# 9DOF-Razor-v23.net
KiCad netlist of a schematic drawn in EAGLE
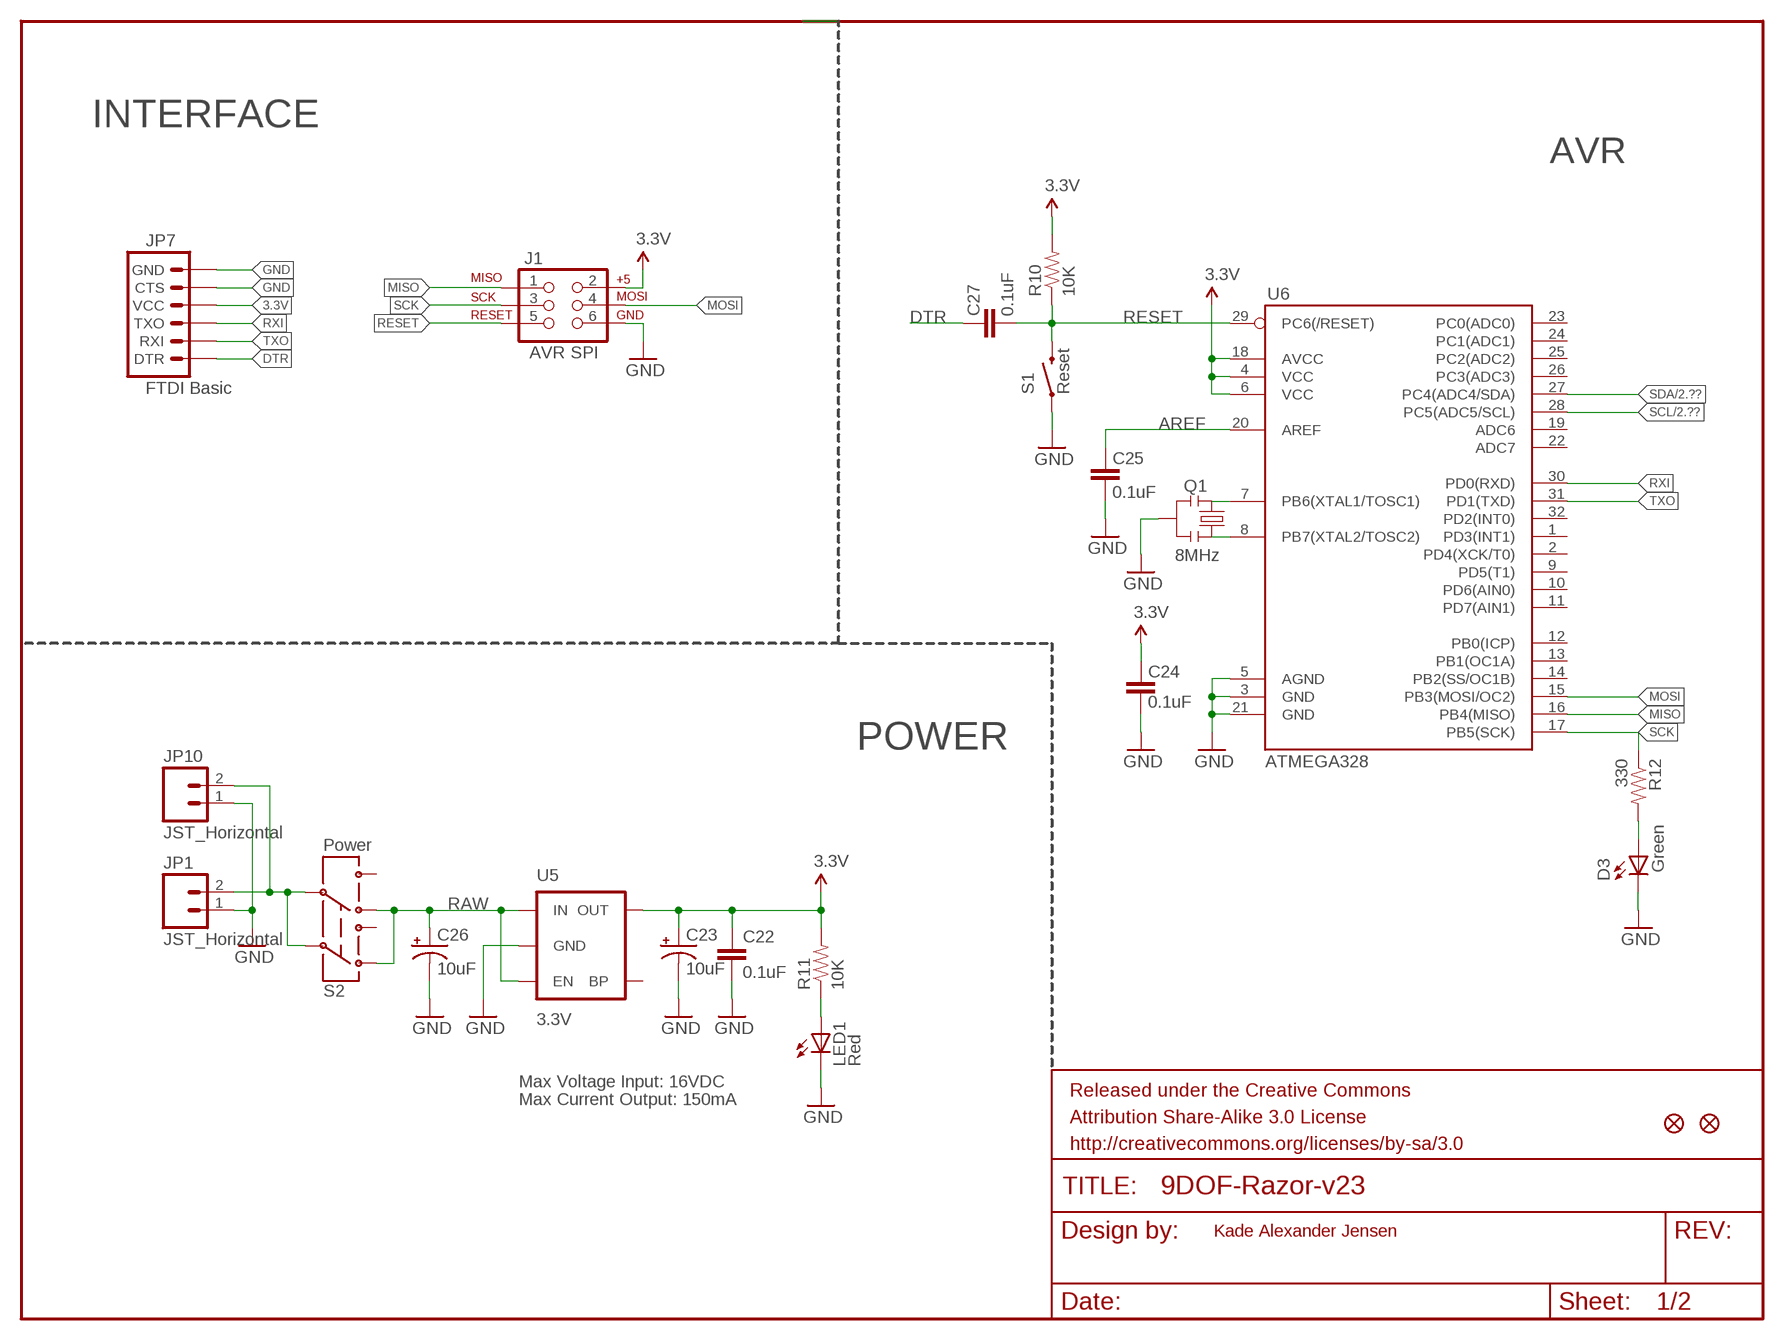
[diagram p0: schematic, sheet 1]
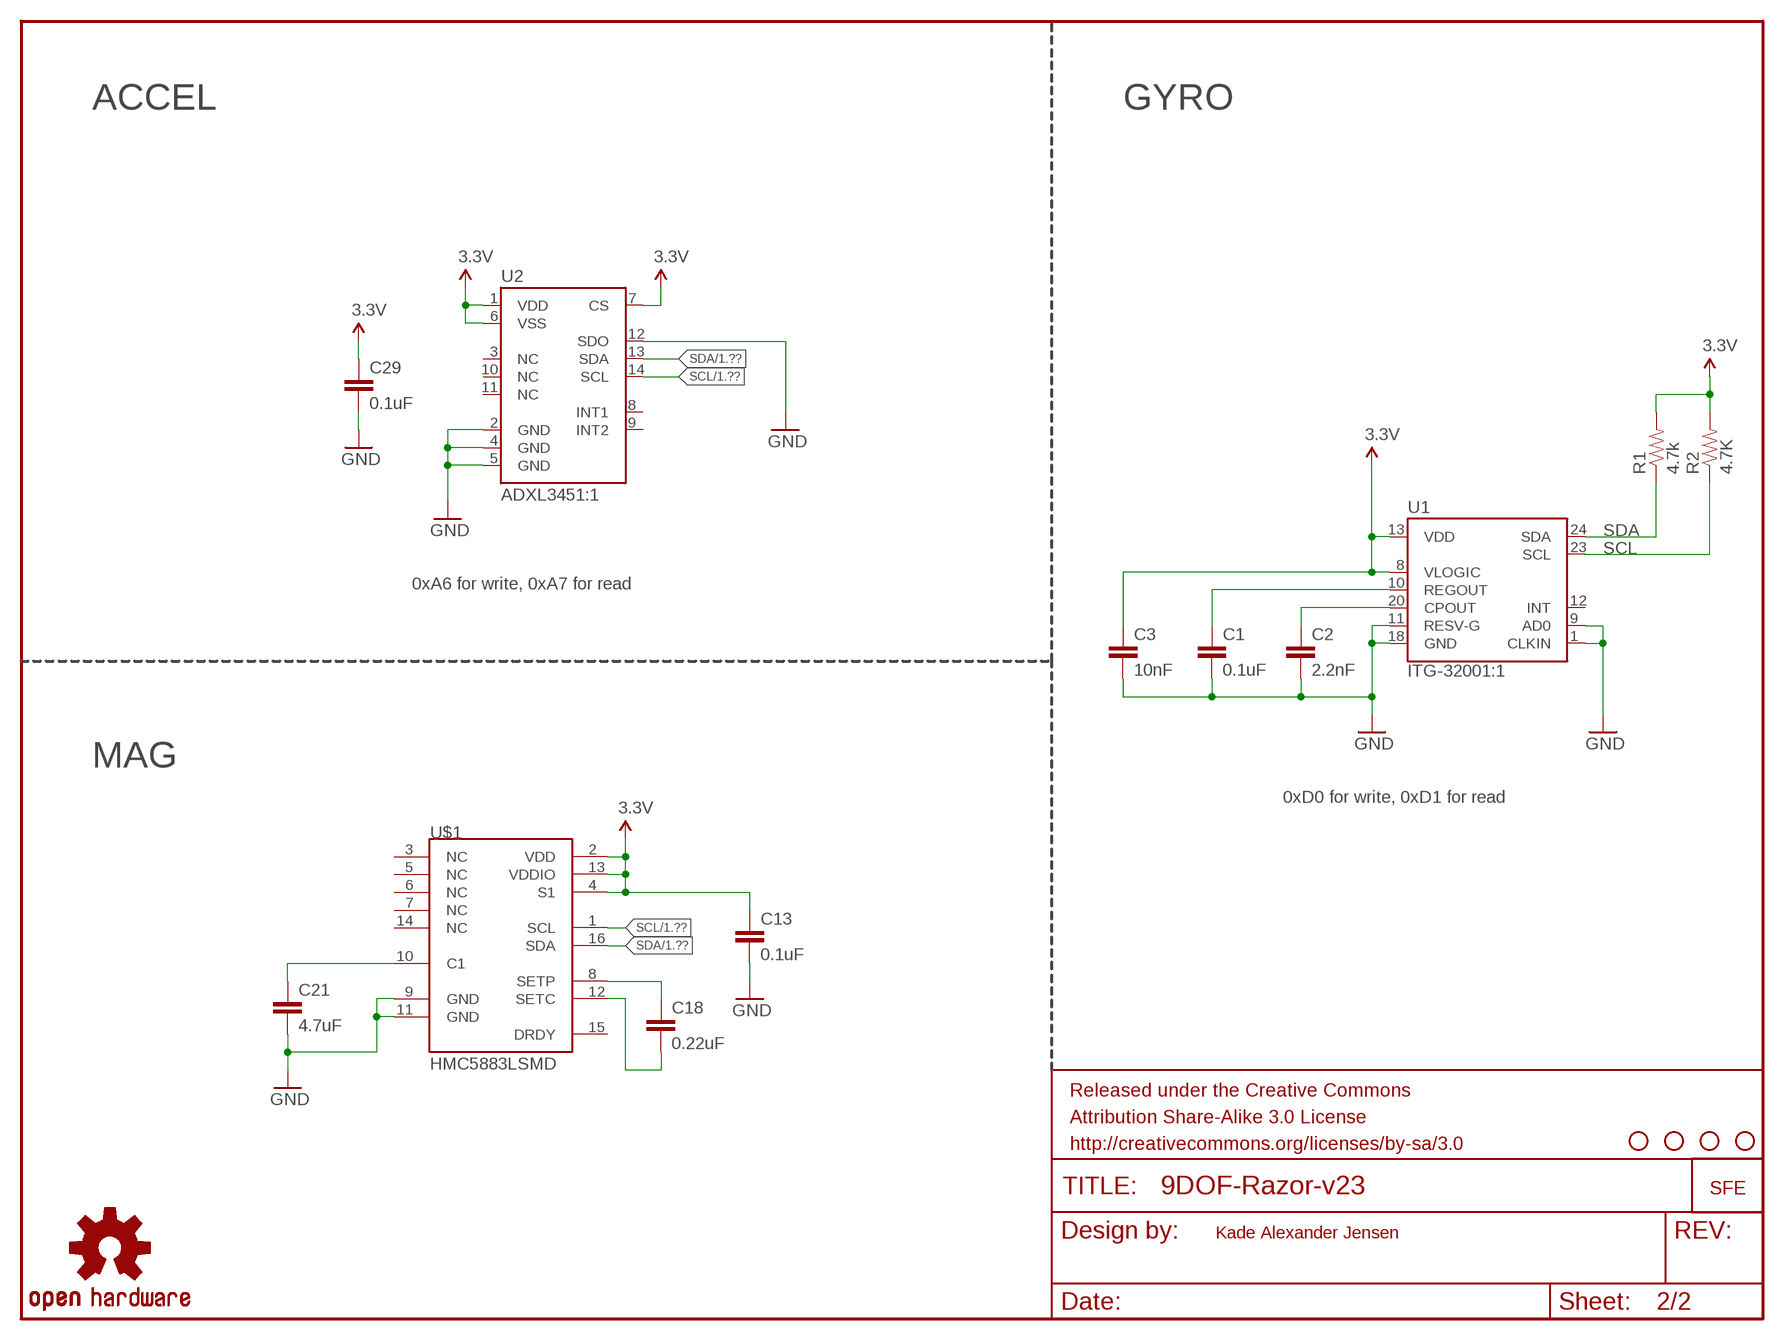
[diagram p1: schematic, sheet 2]

(export (version "E")
  (design (tool "Eeschema 10.0.6"))
  (components
    (comp (ref "C22")
      (value "0.1uF")
      (footprint "eagle-import:0603-CAP")
      (libsource (lib "eagle-import") (part "CAP0603-CAP"))
    )
    (comp (ref "C23")
      (value "10uF")
      (footprint "eagle-import:EIA3216")
      (libsource (lib "eagle-import") (part "CAP_POL1206"))
    )
    (comp (ref "C24")
      (value "0.1uF")
      (footprint "eagle-import:0603-CAP")
      (libsource (lib "eagle-import") (part "CAP0603-CAP"))
    )
    (comp (ref "C25")
      (value "0.1uF")
      (footprint "eagle-import:0603-CAP")
      (libsource (lib "eagle-import") (part "CAP0603-CAP"))
    )
    (comp (ref "C26")
      (value "10uF")
      (footprint "eagle-import:EIA3216")
      (libsource (lib "eagle-import") (part "CAP_POL1206"))
    )
    (comp (ref "C27")
      (value "0.1uF")
      (footprint "eagle-import:0603-CAP")
      (libsource (lib "eagle-import") (part "CAP0603-CAP"))
    )
    (comp (ref "D3")
      (value "Green")
      (footprint "eagle-import:LED-0603")
      (libsource (lib "eagle-import") (part "LED0603"))
    )
    (comp (ref "J1")
      (value "AVR_SPI_PRG_6PTH")
      (footprint "eagle-import:2X3")
      (libsource (lib "eagle-import") (part "AVR_SPI_PRG_6PTH"))
    )
    (comp (ref "JP1")
      (value "JST_Horizontal")
      (footprint "eagle-import:JST-2-SMD")
      (libsource (lib "eagle-import") (part "M02-JST-2MM-SMT"))
    )
    (comp (ref "JP7")
      (value "FTDI Basic")
      (footprint "eagle-import:1X06")
      (libsource (lib "eagle-import") (part "ARDUINO_SERIAL_PROGRAMPTH"))
    )
    (comp (ref "JP10")
      (value "JST_Horizontal")
      (footprint "eagle-import:1X02")
      (libsource (lib "eagle-import") (part "M02PTH"))
    )
    (comp (ref "JP11")
      (value "FIDUCIAL1X2.5")
      (footprint "eagle-import:FIDUCIAL-1X2.5")
      (libsource (lib "eagle-import") (part "FIDUCIAL1X2.5"))
    )
    (comp (ref "JP12")
      (value "FIDUCIAL1X2.5")
      (footprint "eagle-import:FIDUCIAL-1X2.5")
      (libsource (lib "eagle-import") (part "FIDUCIAL1X2.5"))
    )
    (comp (ref "LED1")
      (value "Red")
      (footprint "eagle-import:LED-0603")
      (libsource (lib "eagle-import") (part "LED0603"))
    )
    (comp (ref "Q1")
      (value "8MHz")
      (footprint "eagle-import:RESONATOR-SMD")
      (libsource (lib "eagle-import") (part "RESONATORSMD"))
    )
    (comp (ref "R10")
      (value "10K")
      (footprint "eagle-import:0603-RES")
      (libsource (lib "eagle-import") (part "RESISTOR0603-RES"))
    )
    (comp (ref "R11")
      (value "10K")
      (footprint "eagle-import:0603-RES")
      (libsource (lib "eagle-import") (part "RESISTOR0603-RES"))
    )
    (comp (ref "R12")
      (value "330")
      (footprint "eagle-import:0603-RES")
      (libsource (lib "eagle-import") (part "RESISTOR0603-RES"))
    )
    (comp (ref "S1")
      (value "Reset")
      (footprint "eagle-import:TACTILE_SWITCH_SMD")
      (libsource (lib "eagle-import") (part "SWITCH-MOMENTARY-2SMD"))
    )
    (comp (ref "S2")
      (value "Power")
      (footprint "eagle-import:AYZ0202")
      (libsource (lib "eagle-import") (part "SWITCH-DPDTSMD"))
    )
    (comp (ref "U5")
      (value "3.3V")
      (footprint "eagle-import:SOT23-5")
      (libsource (lib "eagle-import") (part "V_REG_LDOSMD"))
    )
    (comp (ref "U6")
      (value "ATMEGA328")
      (footprint "eagle-import:TQFP32-08")
      (libsource (lib "eagle-import") (part "ATMEGA168"))
    )
    (comp (ref "C1")
      (value "0.1uF")
      (footprint "eagle-import:0603-CAP")
      (libsource (lib "eagle-import") (part "CAP0603-CAP"))
    )
    (comp (ref "C2")
      (value "2.2nF")
      (footprint "eagle-import:0603-CAP")
      (libsource (lib "eagle-import") (part "CAP0603-CAP"))
    )
    (comp (ref "C3")
      (value "10nF")
      (footprint "eagle-import:0603-CAP")
      (libsource (lib "eagle-import") (part "CAP0603-CAP"))
    )
    (comp (ref "C13")
      (value "0.1uF")
      (footprint "eagle-import:0603-CAP")
      (libsource (lib "eagle-import") (part "CAP0603-CAP"))
    )
    (comp (ref "C18")
      (value "0.22uF")
      (footprint "eagle-import:0603-CAP")
      (libsource (lib "eagle-import") (part "CAP0603-CAP"))
    )
    (comp (ref "C21")
      (value "4.7uF")
      (footprint "eagle-import:0603-CAP")
      (libsource (lib "eagle-import") (part "CAP0603-CAP"))
    )
    (comp (ref "C29")
      (value "0.1uF")
      (footprint "eagle-import:0603-CAP")
      (libsource (lib "eagle-import") (part "CAP0603-CAP"))
    )
    (comp (ref "JP2")
      (value "STAND-OFF")
      (footprint "eagle-import:STAND-OFF")
      (libsource (lib "eagle-import") (part "STAND-OFF"))
    )
    (comp (ref "JP3")
      (value "LOGO-SFENEW")
      (footprint "eagle-import:SFE-NEW-WEBLOGO")
      (libsource (lib "eagle-import") (part "LOGO-SFENEW"))
    )
    (comp (ref "JP4")
      (value "STAND-OFF")
      (footprint "eagle-import:STAND-OFF")
      (libsource (lib "eagle-import") (part "STAND-OFF"))
    )
    (comp (ref "JP5")
      (value "STAND-OFF")
      (footprint "eagle-import:STAND-OFF")
      (libsource (lib "eagle-import") (part "STAND-OFF"))
    )
    (comp (ref "JP6")
      (value "STAND-OFF")
      (footprint "eagle-import:STAND-OFF")
      (libsource (lib "eagle-import") (part "STAND-OFF"))
    )
    (comp (ref "R1")
      (value "4.7k")
      (footprint "eagle-import:0603-RES")
      (libsource (lib "eagle-import") (part "RESISTOR0603-RES"))
    )
    (comp (ref "R2")
      (value "4.7K")
      (footprint "eagle-import:0603-RES")
      (libsource (lib "eagle-import") (part "RESISTOR0603-RES"))
    )
    (comp (ref "U$1")
      (value "HMC5883LSMD")
      (footprint "eagle-import:16LPCC")
      (libsource (lib "eagle-import") (part "HMC5883LSMD"))
    )
    (comp (ref "U$4")
      (value "OSHW-LOGOL")
      (footprint "eagle-import:OSHW-LOGO-L")
      (libsource (lib "eagle-import") (part "OSHW-LOGOL"))
    )
    (comp (ref "U1")
      (value "ITG-32001:1")
      (footprint "eagle-import:QFN-24_ITG3200_1_1")
      (libsource (lib "eagle-import") (part "ITG-32001{colon}1"))
    )
    (comp (ref "U2")
      (value "ADXL3451:1")
      (footprint "eagle-import:LGA14")
      (libsource (lib "eagle-import") (part "ADXL3451{colon}1"))
    )
  )
  (nets
    (net (code "1") (name "3.3V") (class "Default")
      (node (ref "C13") (pin "1") (pinfunction "1_1") (pintype "passive"))
      (node (ref "C22") (pin "1") (pinfunction "1_1") (pintype "passive"))
      (node (ref "C23") (pin "A") (pinfunction "+_A") (pintype "passive"))
      (node (ref "C24") (pin "2") (pinfunction "2_2") (pintype "passive"))
      (node (ref "C29") (pin "1") (pinfunction "1_1") (pintype "passive"))
      (node (ref "C3") (pin "1") (pinfunction "1_1") (pintype "passive"))
      (node (ref "J1") (pin "2") (pinfunction "2_2") (pintype "passive"))
      (node (ref "JP7") (pin "4") (pinfunction "VCC_4") (pintype "passive"))
      (node (ref "R1") (pin "2") (pinfunction "2_2") (pintype "passive"))
      (node (ref "R10") (pin "2") (pinfunction "2_2") (pintype "passive"))
      (node (ref "R11") (pin "2") (pinfunction "2_2") (pintype "passive"))
      (node (ref "R2") (pin "2") (pinfunction "2_2") (pintype "passive"))
      (node (ref "U$1") (pin "13") (pinfunction "VDDIO_13") (pintype "bidirectional"))
      (node (ref "U$1") (pin "2") (pinfunction "VDD_2") (pintype "bidirectional"))
      (node (ref "U$1") (pin "4") (pinfunction "S1_4") (pintype "bidirectional"))
      (node (ref "U1") (pin "13") (pinfunction "VDD_13") (pintype "bidirectional"))
      (node (ref "U1") (pin "8") (pinfunction "VLOGIC_8") (pintype "bidirectional"))
      (node (ref "U2") (pin "1") (pinfunction "VDD_1") (pintype "bidirectional"))
      (node (ref "U2") (pin "6") (pinfunction "VSS_6") (pintype "bidirectional"))
      (node (ref "U2") (pin "7") (pinfunction "CS_7") (pintype "bidirectional"))
      (node (ref "U5") (pin "5") (pinfunction "OUT_5") (pintype "passive"))
      (node (ref "U6") (pin "18") (pinfunction "AVCC_18") (pintype "bidirectional"))
      (node (ref "U6") (pin "4") (pinfunction "VCC_4") (pintype "bidirectional"))
      (node (ref "U6") (pin "6") (pinfunction "VCC_6") (pintype "bidirectional"))
    )
    (net (code "2") (name "AREF") (class "Default")
      (node (ref "C25") (pin "2") (pinfunction "2_2") (pintype "passive"))
      (node (ref "U6") (pin "20") (pinfunction "AREF_20") (pintype "bidirectional"))
    )
    (net (code "3") (name "DTR") (class "Default")
      (node (ref "C27") (pin "2") (pinfunction "2_2") (pintype "passive"))
      (node (ref "JP7") (pin "1") (pinfunction "DTR_1") (pintype "passive"))
    )
    (net (code "4") (name "GND") (class "Default")
      (node (ref "C1") (pin "2") (pinfunction "2_2") (pintype "passive"))
      (node (ref "C13") (pin "2") (pinfunction "2_2") (pintype "passive"))
      (node (ref "C2") (pin "2") (pinfunction "2_2") (pintype "passive"))
      (node (ref "C21") (pin "2") (pinfunction "2_2") (pintype "passive"))
      (node (ref "C22") (pin "2") (pinfunction "2_2") (pintype "passive"))
      (node (ref "C23") (pin "C") (pinfunction "-_C") (pintype "passive"))
      (node (ref "C24") (pin "1") (pinfunction "1_1") (pintype "passive"))
      (node (ref "C25") (pin "1") (pinfunction "1_1") (pintype "passive"))
      (node (ref "C26") (pin "C") (pinfunction "-_C") (pintype "passive"))
      (node (ref "C29") (pin "2") (pinfunction "2_2") (pintype "passive"))
      (node (ref "C3") (pin "2") (pinfunction "2_2") (pintype "passive"))
      (node (ref "D3") (pin "C") (pinfunction "C_C") (pintype "passive"))
      (node (ref "J1") (pin "6") (pinfunction "6_6") (pintype "passive"))
      (node (ref "JP1") (pin "1") (pinfunction "1_1") (pintype "passive"))
      (node (ref "JP10") (pin "1") (pinfunction "1_1") (pintype "passive"))
      (node (ref "JP7") (pin "5") (pinfunction "CTS_5") (pintype "passive"))
      (node (ref "JP7") (pin "6") (pinfunction "GND_6") (pintype "passive"))
      (node (ref "LED1") (pin "C") (pinfunction "C_C") (pintype "passive"))
      (node (ref "Q1") (pin "2") (pinfunction "2_2") (pintype "passive"))
      (node (ref "S1") (pin "1") (pinfunction "1_1") (pintype "passive"))
      (node (ref "U$1") (pin "11") (pinfunction "GND_11") (pintype "bidirectional"))
      (node (ref "U$1") (pin "9") (pinfunction "GND_9") (pintype "bidirectional"))
      (node (ref "U1") (pin "1") (pinfunction "CLKIN_1") (pintype "bidirectional"))
      (node (ref "U1") (pin "11") (pinfunction "RESV-G_11") (pintype "bidirectional"))
      (node (ref "U1") (pin "18") (pinfunction "GND_18") (pintype "bidirectional"))
      (node (ref "U1") (pin "9") (pinfunction "AD0_9") (pintype "bidirectional"))
      (node (ref "U2") (pin "12") (pinfunction "SDO_12") (pintype "bidirectional"))
      (node (ref "U2") (pin "2") (pinfunction "GND_2") (pintype "bidirectional"))
      (node (ref "U2") (pin "4") (pinfunction "GND_4") (pintype "bidirectional"))
      (node (ref "U2") (pin "5") (pinfunction "GND_5") (pintype "bidirectional"))
      (node (ref "U5") (pin "2") (pinfunction "GND_2") (pintype "input"))
      (node (ref "U6") (pin "21") (pinfunction "GND_21") (pintype "bidirectional"))
      (node (ref "U6") (pin "3") (pinfunction "GND_3") (pintype "bidirectional"))
      (node (ref "U6") (pin "5") (pinfunction "AGND_5") (pintype "bidirectional"))
    )
    (net (code "5") (name "MISO") (class "Default")
      (node (ref "J1") (pin "1") (pinfunction "1_1") (pintype "passive"))
      (node (ref "U6") (pin "16") (pinfunction "PB4(MISO)_16") (pintype "bidirectional"))
    )
    (net (code "6") (name "MOSI") (class "Default")
      (node (ref "J1") (pin "4") (pinfunction "4_4") (pintype "passive"))
      (node (ref "U6") (pin "15") (pinfunction "PB3(MOSI/OC2)_15") (pintype "bidirectional"))
    )
    (net (code "7") (name "Net-(D3-PadA)") (class "Default")
      (node (ref "D3") (pin "A") (pinfunction "A_A") (pintype "passive"))
      (node (ref "R12") (pin "2") (pinfunction "2_2") (pintype "passive"))
    )
    (net (code "8") (name "Net-(JP1-Pad2)") (class "Default")
      (node (ref "JP1") (pin "2") (pinfunction "2_2") (pintype "passive"))
      (node (ref "JP10") (pin "2") (pinfunction "2_2") (pintype "passive"))
      (node (ref "S2") (pin "2") (pinfunction "2_2") (pintype "bidirectional"))
      (node (ref "S2") (pin "5") (pinfunction "5_5") (pintype "bidirectional"))
    )
    (net (code "9") (name "Net-(LED1-PadA)") (class "Default")
      (node (ref "LED1") (pin "A") (pinfunction "A_A") (pintype "passive"))
      (node (ref "R11") (pin "1") (pinfunction "1_1") (pintype "passive"))
    )
    (net (code "10") (name "Net-(U$1-C1)") (class "Default")
      (node (ref "C21") (pin "1") (pinfunction "1_1") (pintype "passive"))
      (node (ref "U$1") (pin "10") (pinfunction "C1_10") (pintype "bidirectional"))
    )
    (net (code "11") (name "Net-(U$1-SETC)") (class "Default")
      (node (ref "C18") (pin "1") (pinfunction "1_1") (pintype "passive"))
      (node (ref "U$1") (pin "12") (pinfunction "SETC_12") (pintype "bidirectional"))
    )
    (net (code "12") (name "Net-(U$1-SETP)") (class "Default")
      (node (ref "C18") (pin "2") (pinfunction "2_2") (pintype "passive"))
      (node (ref "U$1") (pin "8") (pinfunction "SETP_8") (pintype "bidirectional"))
    )
    (net (code "13") (name "Net-(U1-CPOUT)") (class "Default")
      (node (ref "C2") (pin "1") (pinfunction "1_1") (pintype "passive"))
      (node (ref "U1") (pin "20") (pinfunction "CPOUT_20") (pintype "bidirectional"))
    )
    (net (code "14") (name "Net-(U1-REGOUT)") (class "Default")
      (node (ref "C1") (pin "1") (pinfunction "1_1") (pintype "passive"))
      (node (ref "U1") (pin "10") (pinfunction "REGOUT_10") (pintype "bidirectional"))
    )
    (net (code "15") (name "Net-(U6-PB6(XTAL1{slash}TOSC1))") (class "Default")
      (node (ref "Q1") (pin "3") (pinfunction "3_3") (pintype "passive"))
      (node (ref "U6") (pin "7") (pinfunction "PB6(XTAL1/TOSC1)_7") (pintype "bidirectional"))
    )
    (net (code "16") (name "Net-(U6-PB7(XTAL2{slash}TOSC2))") (class "Default")
      (node (ref "Q1") (pin "1") (pinfunction "1_1") (pintype "passive"))
      (node (ref "U6") (pin "8") (pinfunction "PB7(XTAL2/TOSC2)_8") (pintype "bidirectional"))
    )
    (net (code "17") (name "RAW") (class "Default")
      (node (ref "C26") (pin "A") (pinfunction "+_A") (pintype "passive"))
      (node (ref "S2") (pin "1") (pinfunction "1_1") (pintype "bidirectional"))
      (node (ref "S2") (pin "4") (pinfunction "4_4") (pintype "bidirectional"))
      (node (ref "U5") (pin "1") (pinfunction "IN_1") (pintype "input"))
      (node (ref "U5") (pin "3") (pinfunction "EN_3") (pintype "input"))
    )
    (net (code "18") (name "RESET") (class "Default")
      (node (ref "C27") (pin "1") (pinfunction "1_1") (pintype "passive"))
      (node (ref "J1") (pin "5") (pinfunction "5_5") (pintype "passive"))
      (node (ref "R10") (pin "1") (pinfunction "1_1") (pintype "passive"))
      (node (ref "S1") (pin "3") (pinfunction "2_3") (pintype "passive"))
      (node (ref "U6") (pin "29") (pinfunction "PC6(/RESET)_29") (pintype "bidirectional"))
    )
    (net (code "19") (name "RXI") (class "Default")
      (node (ref "JP7") (pin "3") (pinfunction "TXO_3") (pintype "passive"))
      (node (ref "U6") (pin "30") (pinfunction "PD0(RXD)_30") (pintype "bidirectional"))
    )
    (net (code "20") (name "SCK") (class "Default")
      (node (ref "J1") (pin "3") (pinfunction "3_3") (pintype "passive"))
      (node (ref "R12") (pin "1") (pinfunction "1_1") (pintype "passive"))
      (node (ref "U6") (pin "17") (pinfunction "PB5(SCK)_17") (pintype "bidirectional"))
    )
    (net (code "21") (name "SCL") (class "Default")
      (node (ref "R2") (pin "1") (pinfunction "1_1") (pintype "passive"))
      (node (ref "U$1") (pin "1") (pinfunction "SCL_1") (pintype "bidirectional"))
      (node (ref "U1") (pin "23") (pinfunction "SCL_23") (pintype "bidirectional"))
      (node (ref "U2") (pin "14") (pinfunction "SCL_14") (pintype "bidirectional"))
      (node (ref "U6") (pin "28") (pinfunction "PC5(ADC5/SCL)_28") (pintype "bidirectional"))
    )
    (net (code "22") (name "SDA") (class "Default")
      (node (ref "R1") (pin "1") (pinfunction "1_1") (pintype "passive"))
      (node (ref "U$1") (pin "16") (pinfunction "SDA_16") (pintype "bidirectional"))
      (node (ref "U1") (pin "24") (pinfunction "SDA_24") (pintype "bidirectional"))
      (node (ref "U2") (pin "13") (pinfunction "SDA_13") (pintype "bidirectional"))
      (node (ref "U6") (pin "27") (pinfunction "PC4(ADC4/SDA)_27") (pintype "bidirectional"))
    )
    (net (code "23") (name "TXO") (class "Default")
      (node (ref "JP7") (pin "2") (pinfunction "RXI_2") (pintype "passive"))
      (node (ref "U6") (pin "31") (pinfunction "PD1(TXD)_31") (pintype "bidirectional"))
    )
    (net (code "24") (name "unconnected-(S2-Pad3)") (class "Default")
      (node (ref "S2") (pin "3") (pinfunction "3_3") (pintype "bidirectional"))
    )
    (net (code "25") (name "unconnected-(S2-Pad6)") (class "Default")
      (node (ref "S2") (pin "6") (pinfunction "6_6") (pintype "bidirectional"))
    )
    (net (code "26") (name "unconnected-(U$1-DRDY-Pad15)") (class "Default")
      (node (ref "U$1") (pin "15") (pinfunction "DRDY_15") (pintype "bidirectional"))
    )
    (net (code "27") (name "unconnected-(U$1-NC-Pad3)") (class "Default")
      (node (ref "U$1") (pin "3") (pinfunction "NC_3") (pintype "bidirectional"))
    )
    (net (code "28") (name "unconnected-(U$1-NC-Pad5)") (class "Default")
      (node (ref "U$1") (pin "5") (pinfunction "NC_5") (pintype "bidirectional"))
    )
    (net (code "29") (name "unconnected-(U$1-NC-Pad6)") (class "Default")
      (node (ref "U$1") (pin "6") (pinfunction "NC_6") (pintype "bidirectional"))
    )
    (net (code "30") (name "unconnected-(U$1-NC-Pad7)") (class "Default")
      (node (ref "U$1") (pin "7") (pinfunction "NC_7") (pintype "bidirectional"))
    )
    (net (code "31") (name "unconnected-(U$1-NC-Pad14)") (class "Default")
      (node (ref "U$1") (pin "14") (pinfunction "NC_14") (pintype "bidirectional"))
    )
    (net (code "32") (name "unconnected-(U1-INT-Pad12)") (class "Default")
      (node (ref "U1") (pin "12") (pinfunction "INT_12") (pintype "bidirectional"))
    )
    (net (code "33") (name "unconnected-(U2-INT1-Pad8)") (class "Default")
      (node (ref "U2") (pin "8") (pinfunction "INT1_8") (pintype "bidirectional"))
    )
    (net (code "34") (name "unconnected-(U2-INT2-Pad9)") (class "Default")
      (node (ref "U2") (pin "9") (pinfunction "INT2_9") (pintype "bidirectional"))
    )
    (net (code "35") (name "unconnected-(U2-NC-Pad3)") (class "Default")
      (node (ref "U2") (pin "3") (pinfunction "NC_3") (pintype "bidirectional"))
    )
    (net (code "36") (name "unconnected-(U2-NC-Pad10)") (class "Default")
      (node (ref "U2") (pin "10") (pinfunction "NC_10") (pintype "bidirectional"))
    )
    (net (code "37") (name "unconnected-(U2-NC-Pad11)") (class "Default")
      (node (ref "U2") (pin "11") (pinfunction "NC_11") (pintype "bidirectional"))
    )
    (net (code "38") (name "unconnected-(U5-BP-Pad4)") (class "Default")
      (node (ref "U5") (pin "4") (pinfunction "BP_4") (pintype "input"))
    )
    (net (code "39") (name "unconnected-(U6-ADC6-Pad19)") (class "Default")
      (node (ref "U6") (pin "19") (pinfunction "ADC6_19") (pintype "bidirectional"))
    )
    (net (code "40") (name "unconnected-(U6-ADC7-Pad22)") (class "Default")
      (node (ref "U6") (pin "22") (pinfunction "ADC7_22") (pintype "bidirectional"))
    )
    (net (code "41") (name "unconnected-(U6-PB0(ICP)-Pad12)") (class "Default")
      (node (ref "U6") (pin "12") (pinfunction "PB0(ICP)_12") (pintype "bidirectional"))
    )
    (net (code "42") (name "unconnected-(U6-PB1(OC1A)-Pad13)") (class "Default")
      (node (ref "U6") (pin "13") (pinfunction "PB1(OC1A)_13") (pintype "bidirectional"))
    )
    (net (code "43") (name "unconnected-(U6-PB2(SS{slash}OC1B)-Pad14)") (class "Default")
      (node (ref "U6") (pin "14") (pinfunction "PB2(SS/OC1B)_14") (pintype "bidirectional"))
    )
    (net (code "44") (name "unconnected-(U6-PC0(ADC0)-Pad23)") (class "Default")
      (node (ref "U6") (pin "23") (pinfunction "PC0(ADC0)_23") (pintype "bidirectional"))
    )
    (net (code "45") (name "unconnected-(U6-PC1(ADC1)-Pad24)") (class "Default")
      (node (ref "U6") (pin "24") (pinfunction "PC1(ADC1)_24") (pintype "bidirectional"))
    )
    (net (code "46") (name "unconnected-(U6-PC2(ADC2)-Pad25)") (class "Default")
      (node (ref "U6") (pin "25") (pinfunction "PC2(ADC2)_25") (pintype "bidirectional"))
    )
    (net (code "47") (name "unconnected-(U6-PC3(ADC3)-Pad26)") (class "Default")
      (node (ref "U6") (pin "26") (pinfunction "PC3(ADC3)_26") (pintype "bidirectional"))
    )
    (net (code "48") (name "unconnected-(U6-PD2(INT0)-Pad32)") (class "Default")
      (node (ref "U6") (pin "32") (pinfunction "PD2(INT0)_32") (pintype "bidirectional"))
    )
    (net (code "49") (name "unconnected-(U6-PD3(INT1)-Pad1)") (class "Default")
      (node (ref "U6") (pin "1") (pinfunction "PD3(INT1)_1") (pintype "bidirectional"))
    )
    (net (code "50") (name "unconnected-(U6-PD4(XCK{slash}T0)-Pad2)") (class "Default")
      (node (ref "U6") (pin "2") (pinfunction "PD4(XCK/T0)_2") (pintype "bidirectional"))
    )
    (net (code "51") (name "unconnected-(U6-PD5(T1)-Pad9)") (class "Default")
      (node (ref "U6") (pin "9") (pinfunction "PD5(T1)_9") (pintype "bidirectional"))
    )
    (net (code "52") (name "unconnected-(U6-PD6(AIN0)-Pad10)") (class "Default")
      (node (ref "U6") (pin "10") (pinfunction "PD6(AIN0)_10") (pintype "bidirectional"))
    )
    (net (code "53") (name "unconnected-(U6-PD7(AIN1)-Pad11)") (class "Default")
      (node (ref "U6") (pin "11") (pinfunction "PD7(AIN1)_11") (pintype "bidirectional"))
    )
  )
)
